# TubesAlt.net
KiCad netlist of a schematic drawn in EAGLE
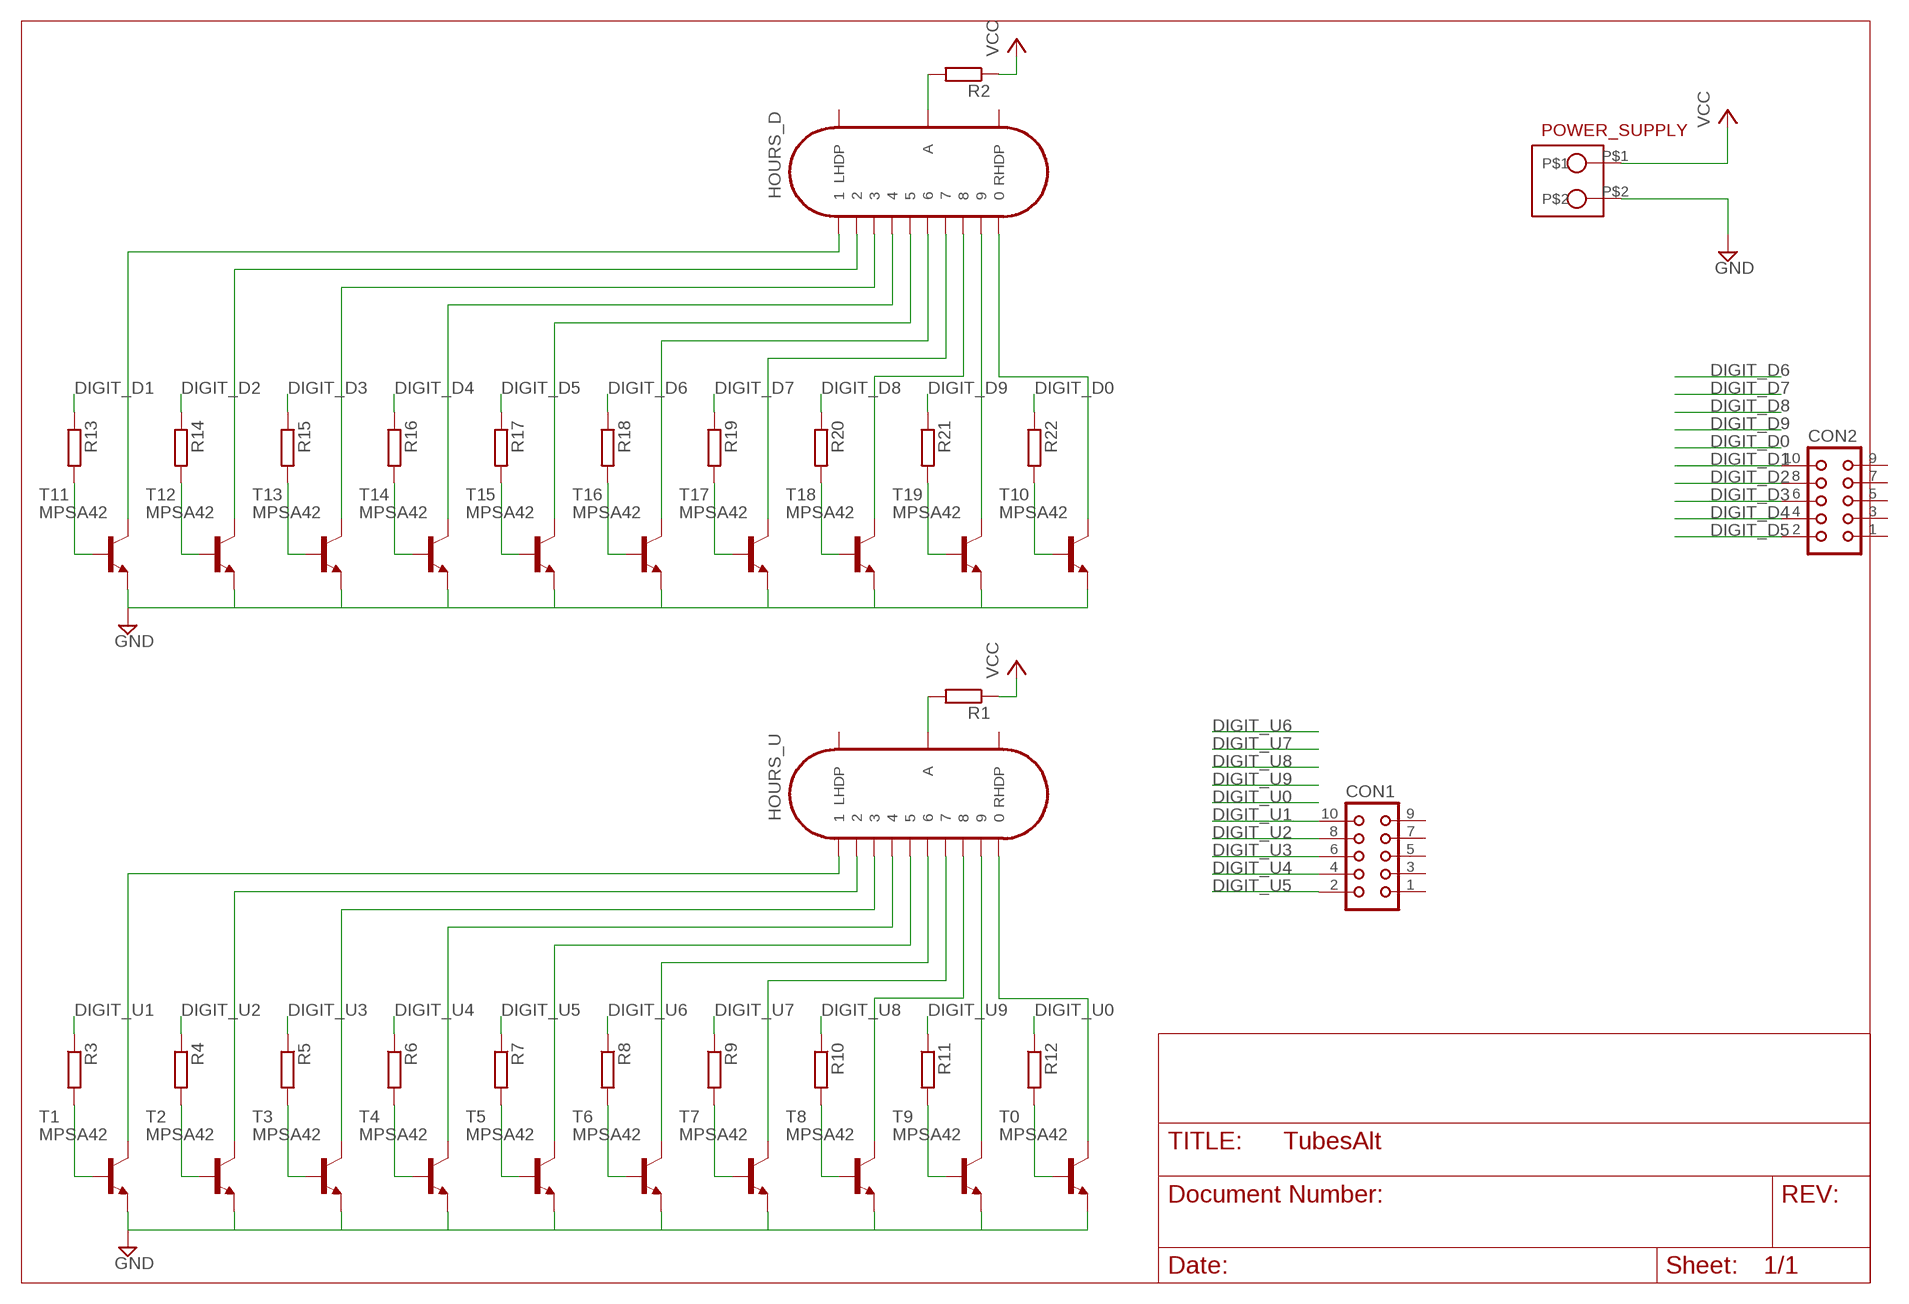
[diagram p0: schematic, sheet 1]

(export (version "E")
  (design (tool "Eeschema 10.0.6"))
  (components
    (comp (ref "CON1")
      (value "CON10")
      (footprint "eagle-import:CON10")
      (libsource (lib "eagle-import") (part "CON10"))
    )
    (comp (ref "CON2")
      (value "CON10")
      (footprint "eagle-import:CON10")
      (libsource (lib "eagle-import") (part "CON10"))
    )
    (comp (ref "HOURS_D")
      (value "IN-14")
      (footprint "eagle-import:IN-14")
      (libsource (lib "eagle-import") (part "IN-14"))
    )
    (comp (ref "HOURS_U")
      (value "IN-14")
      (footprint "eagle-import:IN-14")
      (libsource (lib "eagle-import") (part "IN-14"))
    )
    (comp (ref "POWER_SUPPLY")
      (value "CON_2_SIL")
      (footprint "eagle-import:SIL_2_0.2INCH")
      (libsource (lib "eagle-import") (part "CON_2_SIL"))
    )
    (comp (ref "R1")
      (value "R-EU_0207/10")
      (footprint "eagle-import:0207_10")
      (libsource (lib "eagle-import") (part "R-EU_0207/10"))
    )
    (comp (ref "R2")
      (value "R-EU_0207/10")
      (footprint "eagle-import:0207_10")
      (libsource (lib "eagle-import") (part "R-EU_0207/10"))
    )
    (comp (ref "R3")
      (value "R-EU_0207/10")
      (footprint "eagle-import:0207_10")
      (libsource (lib "eagle-import") (part "R-EU_0207/10"))
    )
    (comp (ref "R4")
      (value "R-EU_0207/10")
      (footprint "eagle-import:0207_10")
      (libsource (lib "eagle-import") (part "R-EU_0207/10"))
    )
    (comp (ref "R5")
      (value "R-EU_0207/10")
      (footprint "eagle-import:0207_10")
      (libsource (lib "eagle-import") (part "R-EU_0207/10"))
    )
    (comp (ref "R6")
      (value "R-EU_0207/10")
      (footprint "eagle-import:0207_10")
      (libsource (lib "eagle-import") (part "R-EU_0207/10"))
    )
    (comp (ref "R7")
      (value "R-EU_0207/10")
      (footprint "eagle-import:0207_10")
      (libsource (lib "eagle-import") (part "R-EU_0207/10"))
    )
    (comp (ref "R8")
      (value "R-EU_0207/10")
      (footprint "eagle-import:0207_10")
      (libsource (lib "eagle-import") (part "R-EU_0207/10"))
    )
    (comp (ref "R9")
      (value "R-EU_0207/10")
      (footprint "eagle-import:0207_10")
      (libsource (lib "eagle-import") (part "R-EU_0207/10"))
    )
    (comp (ref "R10")
      (value "R-EU_0207/10")
      (footprint "eagle-import:0207_10")
      (libsource (lib "eagle-import") (part "R-EU_0207/10"))
    )
    (comp (ref "R11")
      (value "R-EU_0207/10")
      (footprint "eagle-import:0207_10")
      (libsource (lib "eagle-import") (part "R-EU_0207/10"))
    )
    (comp (ref "R12")
      (value "R-EU_0207/10")
      (footprint "eagle-import:0207_10")
      (libsource (lib "eagle-import") (part "R-EU_0207/10"))
    )
    (comp (ref "R13")
      (value "R-EU_0207/10")
      (footprint "eagle-import:0207_10")
      (libsource (lib "eagle-import") (part "R-EU_0207/10"))
    )
    (comp (ref "R14")
      (value "R-EU_0207/10")
      (footprint "eagle-import:0207_10")
      (libsource (lib "eagle-import") (part "R-EU_0207/10"))
    )
    (comp (ref "R15")
      (value "R-EU_0207/10")
      (footprint "eagle-import:0207_10")
      (libsource (lib "eagle-import") (part "R-EU_0207/10"))
    )
    (comp (ref "R16")
      (value "R-EU_0207/10")
      (footprint "eagle-import:0207_10")
      (libsource (lib "eagle-import") (part "R-EU_0207/10"))
    )
    (comp (ref "R17")
      (value "R-EU_0207/10")
      (footprint "eagle-import:0207_10")
      (libsource (lib "eagle-import") (part "R-EU_0207/10"))
    )
    (comp (ref "R18")
      (value "R-EU_0207/10")
      (footprint "eagle-import:0207_10")
      (libsource (lib "eagle-import") (part "R-EU_0207/10"))
    )
    (comp (ref "R19")
      (value "R-EU_0207/10")
      (footprint "eagle-import:0207_10")
      (libsource (lib "eagle-import") (part "R-EU_0207/10"))
    )
    (comp (ref "R20")
      (value "R-EU_0207/10")
      (footprint "eagle-import:0207_10")
      (libsource (lib "eagle-import") (part "R-EU_0207/10"))
    )
    (comp (ref "R21")
      (value "R-EU_0207/10")
      (footprint "eagle-import:0207_10")
      (libsource (lib "eagle-import") (part "R-EU_0207/10"))
    )
    (comp (ref "R22")
      (value "R-EU_0207/10")
      (footprint "eagle-import:0207_10")
      (libsource (lib "eagle-import") (part "R-EU_0207/10"))
    )
    (comp (ref "T0")
      (value "MPSA42")
      (footprint "eagle-import:TO92")
      (libsource (lib "eagle-import") (part "MPSA42"))
    )
    (comp (ref "T1")
      (value "MPSA42")
      (footprint "eagle-import:TO92")
      (libsource (lib "eagle-import") (part "MPSA42"))
    )
    (comp (ref "T2")
      (value "MPSA42")
      (footprint "eagle-import:TO92")
      (libsource (lib "eagle-import") (part "MPSA42"))
    )
    (comp (ref "T3")
      (value "MPSA42")
      (footprint "eagle-import:TO92")
      (libsource (lib "eagle-import") (part "MPSA42"))
    )
    (comp (ref "T4")
      (value "MPSA42")
      (footprint "eagle-import:TO92")
      (libsource (lib "eagle-import") (part "MPSA42"))
    )
    (comp (ref "T5")
      (value "MPSA42")
      (footprint "eagle-import:TO92")
      (libsource (lib "eagle-import") (part "MPSA42"))
    )
    (comp (ref "T6")
      (value "MPSA42")
      (footprint "eagle-import:TO92")
      (libsource (lib "eagle-import") (part "MPSA42"))
    )
    (comp (ref "T7")
      (value "MPSA42")
      (footprint "eagle-import:TO92")
      (libsource (lib "eagle-import") (part "MPSA42"))
    )
    (comp (ref "T8")
      (value "MPSA42")
      (footprint "eagle-import:TO92")
      (libsource (lib "eagle-import") (part "MPSA42"))
    )
    (comp (ref "T9")
      (value "MPSA42")
      (footprint "eagle-import:TO92")
      (libsource (lib "eagle-import") (part "MPSA42"))
    )
    (comp (ref "T10")
      (value "MPSA42")
      (footprint "eagle-import:TO92")
      (libsource (lib "eagle-import") (part "MPSA42"))
    )
    (comp (ref "T11")
      (value "MPSA42")
      (footprint "eagle-import:TO92")
      (libsource (lib "eagle-import") (part "MPSA42"))
    )
    (comp (ref "T12")
      (value "MPSA42")
      (footprint "eagle-import:TO92")
      (libsource (lib "eagle-import") (part "MPSA42"))
    )
    (comp (ref "T13")
      (value "MPSA42")
      (footprint "eagle-import:TO92")
      (libsource (lib "eagle-import") (part "MPSA42"))
    )
    (comp (ref "T14")
      (value "MPSA42")
      (footprint "eagle-import:TO92")
      (libsource (lib "eagle-import") (part "MPSA42"))
    )
    (comp (ref "T15")
      (value "MPSA42")
      (footprint "eagle-import:TO92")
      (libsource (lib "eagle-import") (part "MPSA42"))
    )
    (comp (ref "T16")
      (value "MPSA42")
      (footprint "eagle-import:TO92")
      (libsource (lib "eagle-import") (part "MPSA42"))
    )
    (comp (ref "T17")
      (value "MPSA42")
      (footprint "eagle-import:TO92")
      (libsource (lib "eagle-import") (part "MPSA42"))
    )
    (comp (ref "T18")
      (value "MPSA42")
      (footprint "eagle-import:TO92")
      (libsource (lib "eagle-import") (part "MPSA42"))
    )
    (comp (ref "T19")
      (value "MPSA42")
      (footprint "eagle-import:TO92")
      (libsource (lib "eagle-import") (part "MPSA42"))
    )
  )
  (nets
    (net (code "1") (name "/DIGIT_D0") (class "Default")
      (node (ref "R22") (pin "1") (pinfunction "1_1") (pintype "passive"))
    )
    (net (code "2") (name "/DIGIT_D1") (class "Default")
      (node (ref "CON2") (pin "10") (pinfunction "10_10") (pintype "passive"))
      (node (ref "R13") (pin "1") (pinfunction "1_1") (pintype "passive"))
    )
    (net (code "3") (name "/DIGIT_D2") (class "Default")
      (node (ref "CON2") (pin "8") (pinfunction "8_8") (pintype "passive"))
      (node (ref "R14") (pin "1") (pinfunction "1_1") (pintype "passive"))
    )
    (net (code "4") (name "/DIGIT_D3") (class "Default")
      (node (ref "CON2") (pin "6") (pinfunction "6_6") (pintype "passive"))
      (node (ref "R15") (pin "1") (pinfunction "1_1") (pintype "passive"))
    )
    (net (code "5") (name "/DIGIT_D4") (class "Default")
      (node (ref "CON2") (pin "4") (pinfunction "4_4") (pintype "passive"))
      (node (ref "R16") (pin "1") (pinfunction "1_1") (pintype "passive"))
    )
    (net (code "6") (name "/DIGIT_D5") (class "Default")
      (node (ref "CON2") (pin "2") (pinfunction "2_2") (pintype "passive"))
      (node (ref "R17") (pin "1") (pinfunction "1_1") (pintype "passive"))
    )
    (net (code "7") (name "/DIGIT_D6") (class "Default")
      (node (ref "R18") (pin "1") (pinfunction "1_1") (pintype "passive"))
    )
    (net (code "8") (name "/DIGIT_D7") (class "Default")
      (node (ref "R19") (pin "1") (pinfunction "1_1") (pintype "passive"))
    )
    (net (code "9") (name "/DIGIT_D8") (class "Default")
      (node (ref "R20") (pin "1") (pinfunction "1_1") (pintype "passive"))
    )
    (net (code "10") (name "/DIGIT_D9") (class "Default")
      (node (ref "R21") (pin "1") (pinfunction "1_1") (pintype "passive"))
    )
    (net (code "11") (name "/DIGIT_U0") (class "Default")
      (node (ref "R12") (pin "1") (pinfunction "1_1") (pintype "passive"))
    )
    (net (code "12") (name "/DIGIT_U1") (class "Default")
      (node (ref "CON1") (pin "10") (pinfunction "10_10") (pintype "passive"))
      (node (ref "R3") (pin "1") (pinfunction "1_1") (pintype "passive"))
    )
    (net (code "13") (name "/DIGIT_U2") (class "Default")
      (node (ref "CON1") (pin "8") (pinfunction "8_8") (pintype "passive"))
      (node (ref "R4") (pin "1") (pinfunction "1_1") (pintype "passive"))
    )
    (net (code "14") (name "/DIGIT_U3") (class "Default")
      (node (ref "CON1") (pin "6") (pinfunction "6_6") (pintype "passive"))
      (node (ref "R5") (pin "1") (pinfunction "1_1") (pintype "passive"))
    )
    (net (code "15") (name "/DIGIT_U4") (class "Default")
      (node (ref "CON1") (pin "4") (pinfunction "4_4") (pintype "passive"))
      (node (ref "R6") (pin "1") (pinfunction "1_1") (pintype "passive"))
    )
    (net (code "16") (name "/DIGIT_U5") (class "Default")
      (node (ref "CON1") (pin "2") (pinfunction "2_2") (pintype "passive"))
      (node (ref "R7") (pin "1") (pinfunction "1_1") (pintype "passive"))
    )
    (net (code "17") (name "/DIGIT_U6") (class "Default")
      (node (ref "R8") (pin "1") (pinfunction "1_1") (pintype "passive"))
    )
    (net (code "18") (name "/DIGIT_U7") (class "Default")
      (node (ref "R9") (pin "1") (pinfunction "1_1") (pintype "passive"))
    )
    (net (code "19") (name "/DIGIT_U8") (class "Default")
      (node (ref "R10") (pin "1") (pinfunction "1_1") (pintype "passive"))
    )
    (net (code "20") (name "/DIGIT_U9") (class "Default")
      (node (ref "R11") (pin "1") (pinfunction "1_1") (pintype "passive"))
    )
    (net (code "21") (name "GND") (class "Default")
      (node (ref "POWER_SUPPLY") (pin "P$2") (pinfunction "P$2_P$2") (pintype "bidirectional"))
      (node (ref "T0") (pin "1") (pinfunction "E_1") (pintype "passive"))
      (node (ref "T1") (pin "1") (pinfunction "E_1") (pintype "passive"))
      (node (ref "T10") (pin "1") (pinfunction "E_1") (pintype "passive"))
      (node (ref "T11") (pin "1") (pinfunction "E_1") (pintype "passive"))
      (node (ref "T12") (pin "1") (pinfunction "E_1") (pintype "passive"))
      (node (ref "T13") (pin "1") (pinfunction "E_1") (pintype "passive"))
      (node (ref "T14") (pin "1") (pinfunction "E_1") (pintype "passive"))
      (node (ref "T15") (pin "1") (pinfunction "E_1") (pintype "passive"))
      (node (ref "T16") (pin "1") (pinfunction "E_1") (pintype "passive"))
      (node (ref "T17") (pin "1") (pinfunction "E_1") (pintype "passive"))
      (node (ref "T18") (pin "1") (pinfunction "E_1") (pintype "passive"))
      (node (ref "T19") (pin "1") (pinfunction "E_1") (pintype "passive"))
      (node (ref "T2") (pin "1") (pinfunction "E_1") (pintype "passive"))
      (node (ref "T3") (pin "1") (pinfunction "E_1") (pintype "passive"))
      (node (ref "T4") (pin "1") (pinfunction "E_1") (pintype "passive"))
      (node (ref "T5") (pin "1") (pinfunction "E_1") (pintype "passive"))
      (node (ref "T6") (pin "1") (pinfunction "E_1") (pintype "passive"))
      (node (ref "T7") (pin "1") (pinfunction "E_1") (pintype "passive"))
      (node (ref "T8") (pin "1") (pinfunction "E_1") (pintype "passive"))
      (node (ref "T9") (pin "1") (pinfunction "E_1") (pintype "passive"))
    )
    (net (code "22") (name "Net-(HOURS_D-PadA)") (class "Default")
      (node (ref "HOURS_D") (pin "A") (pinfunction "A_A") (pintype "bidirectional"))
      (node (ref "R2") (pin "2") (pinfunction "2_2") (pintype "passive"))
    )
    (net (code "23") (name "Net-(HOURS_U-PadA)") (class "Default")
      (node (ref "HOURS_U") (pin "A") (pinfunction "A_A") (pintype "bidirectional"))
      (node (ref "R1") (pin "2") (pinfunction "2_2") (pintype "passive"))
    )
    (net (code "24") (name "Net-(T0-B)") (class "Default")
      (node (ref "R12") (pin "2") (pinfunction "2_2") (pintype "passive"))
      (node (ref "T0") (pin "2") (pinfunction "B_2") (pintype "passive"))
    )
    (net (code "25") (name "Net-(T0-C)") (class "Default")
      (node (ref "HOURS_U") (pin "0") (pinfunction "0_0") (pintype "bidirectional"))
      (node (ref "T0") (pin "3") (pinfunction "C_3") (pintype "passive"))
    )
    (net (code "26") (name "Net-(T1-B)") (class "Default")
      (node (ref "R3") (pin "2") (pinfunction "2_2") (pintype "passive"))
      (node (ref "T1") (pin "2") (pinfunction "B_2") (pintype "passive"))
    )
    (net (code "27") (name "Net-(T1-C)") (class "Default")
      (node (ref "HOURS_U") (pin "1") (pinfunction "1_1") (pintype "bidirectional"))
      (node (ref "T1") (pin "3") (pinfunction "C_3") (pintype "passive"))
    )
    (net (code "28") (name "Net-(T2-B)") (class "Default")
      (node (ref "R4") (pin "2") (pinfunction "2_2") (pintype "passive"))
      (node (ref "T2") (pin "2") (pinfunction "B_2") (pintype "passive"))
    )
    (net (code "29") (name "Net-(T2-C)") (class "Default")
      (node (ref "HOURS_U") (pin "2") (pinfunction "2_2") (pintype "bidirectional"))
      (node (ref "T2") (pin "3") (pinfunction "C_3") (pintype "passive"))
    )
    (net (code "30") (name "Net-(T3-B)") (class "Default")
      (node (ref "R5") (pin "2") (pinfunction "2_2") (pintype "passive"))
      (node (ref "T3") (pin "2") (pinfunction "B_2") (pintype "passive"))
    )
    (net (code "31") (name "Net-(T3-C)") (class "Default")
      (node (ref "HOURS_U") (pin "3") (pinfunction "3_3") (pintype "bidirectional"))
      (node (ref "T3") (pin "3") (pinfunction "C_3") (pintype "passive"))
    )
    (net (code "32") (name "Net-(T4-B)") (class "Default")
      (node (ref "R6") (pin "2") (pinfunction "2_2") (pintype "passive"))
      (node (ref "T4") (pin "2") (pinfunction "B_2") (pintype "passive"))
    )
    (net (code "33") (name "Net-(T4-C)") (class "Default")
      (node (ref "HOURS_U") (pin "4") (pinfunction "4_4") (pintype "bidirectional"))
      (node (ref "T4") (pin "3") (pinfunction "C_3") (pintype "passive"))
    )
    (net (code "34") (name "Net-(T5-B)") (class "Default")
      (node (ref "R7") (pin "2") (pinfunction "2_2") (pintype "passive"))
      (node (ref "T5") (pin "2") (pinfunction "B_2") (pintype "passive"))
    )
    (net (code "35") (name "Net-(T5-C)") (class "Default")
      (node (ref "HOURS_U") (pin "5") (pinfunction "5_5") (pintype "bidirectional"))
      (node (ref "T5") (pin "3") (pinfunction "C_3") (pintype "passive"))
    )
    (net (code "36") (name "Net-(T6-B)") (class "Default")
      (node (ref "R8") (pin "2") (pinfunction "2_2") (pintype "passive"))
      (node (ref "T6") (pin "2") (pinfunction "B_2") (pintype "passive"))
    )
    (net (code "37") (name "Net-(T6-C)") (class "Default")
      (node (ref "HOURS_U") (pin "6") (pinfunction "6_6") (pintype "bidirectional"))
      (node (ref "T6") (pin "3") (pinfunction "C_3") (pintype "passive"))
    )
    (net (code "38") (name "Net-(T7-B)") (class "Default")
      (node (ref "R9") (pin "2") (pinfunction "2_2") (pintype "passive"))
      (node (ref "T7") (pin "2") (pinfunction "B_2") (pintype "passive"))
    )
    (net (code "39") (name "Net-(T7-C)") (class "Default")
      (node (ref "HOURS_U") (pin "7") (pinfunction "7_7") (pintype "bidirectional"))
      (node (ref "T7") (pin "3") (pinfunction "C_3") (pintype "passive"))
    )
    (net (code "40") (name "Net-(T8-B)") (class "Default")
      (node (ref "R10") (pin "2") (pinfunction "2_2") (pintype "passive"))
      (node (ref "T8") (pin "2") (pinfunction "B_2") (pintype "passive"))
    )
    (net (code "41") (name "Net-(T8-C)") (class "Default")
      (node (ref "HOURS_U") (pin "8") (pinfunction "8_8") (pintype "bidirectional"))
      (node (ref "T8") (pin "3") (pinfunction "C_3") (pintype "passive"))
    )
    (net (code "42") (name "Net-(T9-B)") (class "Default")
      (node (ref "R11") (pin "2") (pinfunction "2_2") (pintype "passive"))
      (node (ref "T9") (pin "2") (pinfunction "B_2") (pintype "passive"))
    )
    (net (code "43") (name "Net-(T9-C)") (class "Default")
      (node (ref "HOURS_U") (pin "9") (pinfunction "9_9") (pintype "bidirectional"))
      (node (ref "T9") (pin "3") (pinfunction "C_3") (pintype "passive"))
    )
    (net (code "44") (name "Net-(T10-B)") (class "Default")
      (node (ref "R22") (pin "2") (pinfunction "2_2") (pintype "passive"))
      (node (ref "T10") (pin "2") (pinfunction "B_2") (pintype "passive"))
    )
    (net (code "45") (name "Net-(T10-C)") (class "Default")
      (node (ref "HOURS_D") (pin "0") (pinfunction "0_0") (pintype "bidirectional"))
      (node (ref "T10") (pin "3") (pinfunction "C_3") (pintype "passive"))
    )
    (net (code "46") (name "Net-(T11-B)") (class "Default")
      (node (ref "R13") (pin "2") (pinfunction "2_2") (pintype "passive"))
      (node (ref "T11") (pin "2") (pinfunction "B_2") (pintype "passive"))
    )
    (net (code "47") (name "Net-(T11-C)") (class "Default")
      (node (ref "HOURS_D") (pin "1") (pinfunction "1_1") (pintype "bidirectional"))
      (node (ref "T11") (pin "3") (pinfunction "C_3") (pintype "passive"))
    )
    (net (code "48") (name "Net-(T12-B)") (class "Default")
      (node (ref "R14") (pin "2") (pinfunction "2_2") (pintype "passive"))
      (node (ref "T12") (pin "2") (pinfunction "B_2") (pintype "passive"))
    )
    (net (code "49") (name "Net-(T12-C)") (class "Default")
      (node (ref "HOURS_D") (pin "2") (pinfunction "2_2") (pintype "bidirectional"))
      (node (ref "T12") (pin "3") (pinfunction "C_3") (pintype "passive"))
    )
    (net (code "50") (name "Net-(T13-B)") (class "Default")
      (node (ref "R15") (pin "2") (pinfunction "2_2") (pintype "passive"))
      (node (ref "T13") (pin "2") (pinfunction "B_2") (pintype "passive"))
    )
    (net (code "51") (name "Net-(T13-C)") (class "Default")
      (node (ref "HOURS_D") (pin "3") (pinfunction "3_3") (pintype "bidirectional"))
      (node (ref "T13") (pin "3") (pinfunction "C_3") (pintype "passive"))
    )
    (net (code "52") (name "Net-(T14-B)") (class "Default")
      (node (ref "R16") (pin "2") (pinfunction "2_2") (pintype "passive"))
      (node (ref "T14") (pin "2") (pinfunction "B_2") (pintype "passive"))
    )
    (net (code "53") (name "Net-(T14-C)") (class "Default")
      (node (ref "HOURS_D") (pin "4") (pinfunction "4_4") (pintype "bidirectional"))
      (node (ref "T14") (pin "3") (pinfunction "C_3") (pintype "passive"))
    )
    (net (code "54") (name "Net-(T15-B)") (class "Default")
      (node (ref "R17") (pin "2") (pinfunction "2_2") (pintype "passive"))
      (node (ref "T15") (pin "2") (pinfunction "B_2") (pintype "passive"))
    )
    (net (code "55") (name "Net-(T15-C)") (class "Default")
      (node (ref "HOURS_D") (pin "5") (pinfunction "5_5") (pintype "bidirectional"))
      (node (ref "T15") (pin "3") (pinfunction "C_3") (pintype "passive"))
    )
    (net (code "56") (name "Net-(T16-B)") (class "Default")
      (node (ref "R18") (pin "2") (pinfunction "2_2") (pintype "passive"))
      (node (ref "T16") (pin "2") (pinfunction "B_2") (pintype "passive"))
    )
    (net (code "57") (name "Net-(T16-C)") (class "Default")
      (node (ref "HOURS_D") (pin "6") (pinfunction "6_6") (pintype "bidirectional"))
      (node (ref "T16") (pin "3") (pinfunction "C_3") (pintype "passive"))
    )
    (net (code "58") (name "Net-(T17-B)") (class "Default")
      (node (ref "R19") (pin "2") (pinfunction "2_2") (pintype "passive"))
      (node (ref "T17") (pin "2") (pinfunction "B_2") (pintype "passive"))
    )
    (net (code "59") (name "Net-(T17-C)") (class "Default")
      (node (ref "HOURS_D") (pin "7") (pinfunction "7_7") (pintype "bidirectional"))
      (node (ref "T17") (pin "3") (pinfunction "C_3") (pintype "passive"))
    )
    (net (code "60") (name "Net-(T18-B)") (class "Default")
      (node (ref "R20") (pin "2") (pinfunction "2_2") (pintype "passive"))
      (node (ref "T18") (pin "2") (pinfunction "B_2") (pintype "passive"))
    )
    (net (code "61") (name "Net-(T18-C)") (class "Default")
      (node (ref "HOURS_D") (pin "8") (pinfunction "8_8") (pintype "bidirectional"))
      (node (ref "T18") (pin "3") (pinfunction "C_3") (pintype "passive"))
    )
    (net (code "62") (name "Net-(T19-B)") (class "Default")
      (node (ref "R21") (pin "2") (pinfunction "2_2") (pintype "passive"))
      (node (ref "T19") (pin "2") (pinfunction "B_2") (pintype "passive"))
    )
    (net (code "63") (name "Net-(T19-C)") (class "Default")
      (node (ref "HOURS_D") (pin "9") (pinfunction "9_9") (pintype "bidirectional"))
      (node (ref "T19") (pin "3") (pinfunction "C_3") (pintype "passive"))
    )
    (net (code "64") (name "VCC") (class "Default")
      (node (ref "POWER_SUPPLY") (pin "P$1") (pinfunction "P$1_P$1") (pintype "bidirectional"))
      (node (ref "R1") (pin "1") (pinfunction "1_1") (pintype "passive"))
      (node (ref "R2") (pin "1") (pinfunction "1_1") (pintype "passive"))
    )
    (net (code "65") (name "unconnected-(CON1-Pad1)") (class "Default")
      (node (ref "CON1") (pin "1") (pinfunction "1_1") (pintype "passive"))
    )
    (net (code "66") (name "unconnected-(CON1-Pad3)") (class "Default")
      (node (ref "CON1") (pin "3") (pinfunction "3_3") (pintype "passive"))
    )
    (net (code "67") (name "unconnected-(CON1-Pad5)") (class "Default")
      (node (ref "CON1") (pin "5") (pinfunction "5_5") (pintype "passive"))
    )
    (net (code "68") (name "unconnected-(CON1-Pad7)") (class "Default")
      (node (ref "CON1") (pin "7") (pinfunction "7_7") (pintype "passive"))
    )
    (net (code "69") (name "unconnected-(CON1-Pad9)") (class "Default")
      (node (ref "CON1") (pin "9") (pinfunction "9_9") (pintype "passive"))
    )
    (net (code "70") (name "unconnected-(CON2-Pad1)") (class "Default")
      (node (ref "CON2") (pin "1") (pinfunction "1_1") (pintype "passive"))
    )
    (net (code "71") (name "unconnected-(CON2-Pad3)") (class "Default")
      (node (ref "CON2") (pin "3") (pinfunction "3_3") (pintype "passive"))
    )
    (net (code "72") (name "unconnected-(CON2-Pad5)") (class "Default")
      (node (ref "CON2") (pin "5") (pinfunction "5_5") (pintype "passive"))
    )
    (net (code "73") (name "unconnected-(CON2-Pad7)") (class "Default")
      (node (ref "CON2") (pin "7") (pinfunction "7_7") (pintype "passive"))
    )
    (net (code "74") (name "unconnected-(CON2-Pad9)") (class "Default")
      (node (ref "CON2") (pin "9") (pinfunction "9_9") (pintype "passive"))
    )
    (net (code "75") (name "unconnected-(HOURS_D-PadLHDP)") (class "Default")
      (node (ref "HOURS_D") (pin "LHDP") (pinfunction "LHDP_LHDP") (pintype "bidirectional"))
    )
    (net (code "76") (name "unconnected-(HOURS_D-PadRHDP)") (class "Default")
      (node (ref "HOURS_D") (pin "RHDP") (pinfunction "RHDP_RHDP") (pintype "bidirectional"))
    )
    (net (code "77") (name "unconnected-(HOURS_U-PadLHDP)") (class "Default")
      (node (ref "HOURS_U") (pin "LHDP") (pinfunction "LHDP_LHDP") (pintype "bidirectional"))
    )
    (net (code "78") (name "unconnected-(HOURS_U-PadRHDP)") (class "Default")
      (node (ref "HOURS_U") (pin "RHDP") (pinfunction "RHDP_RHDP") (pintype "bidirectional"))
    )
  )
)
